# Grove_Base_Cape_for_BeagleBone_v2_0.net
KiCad netlist of a schematic drawn in EAGLE
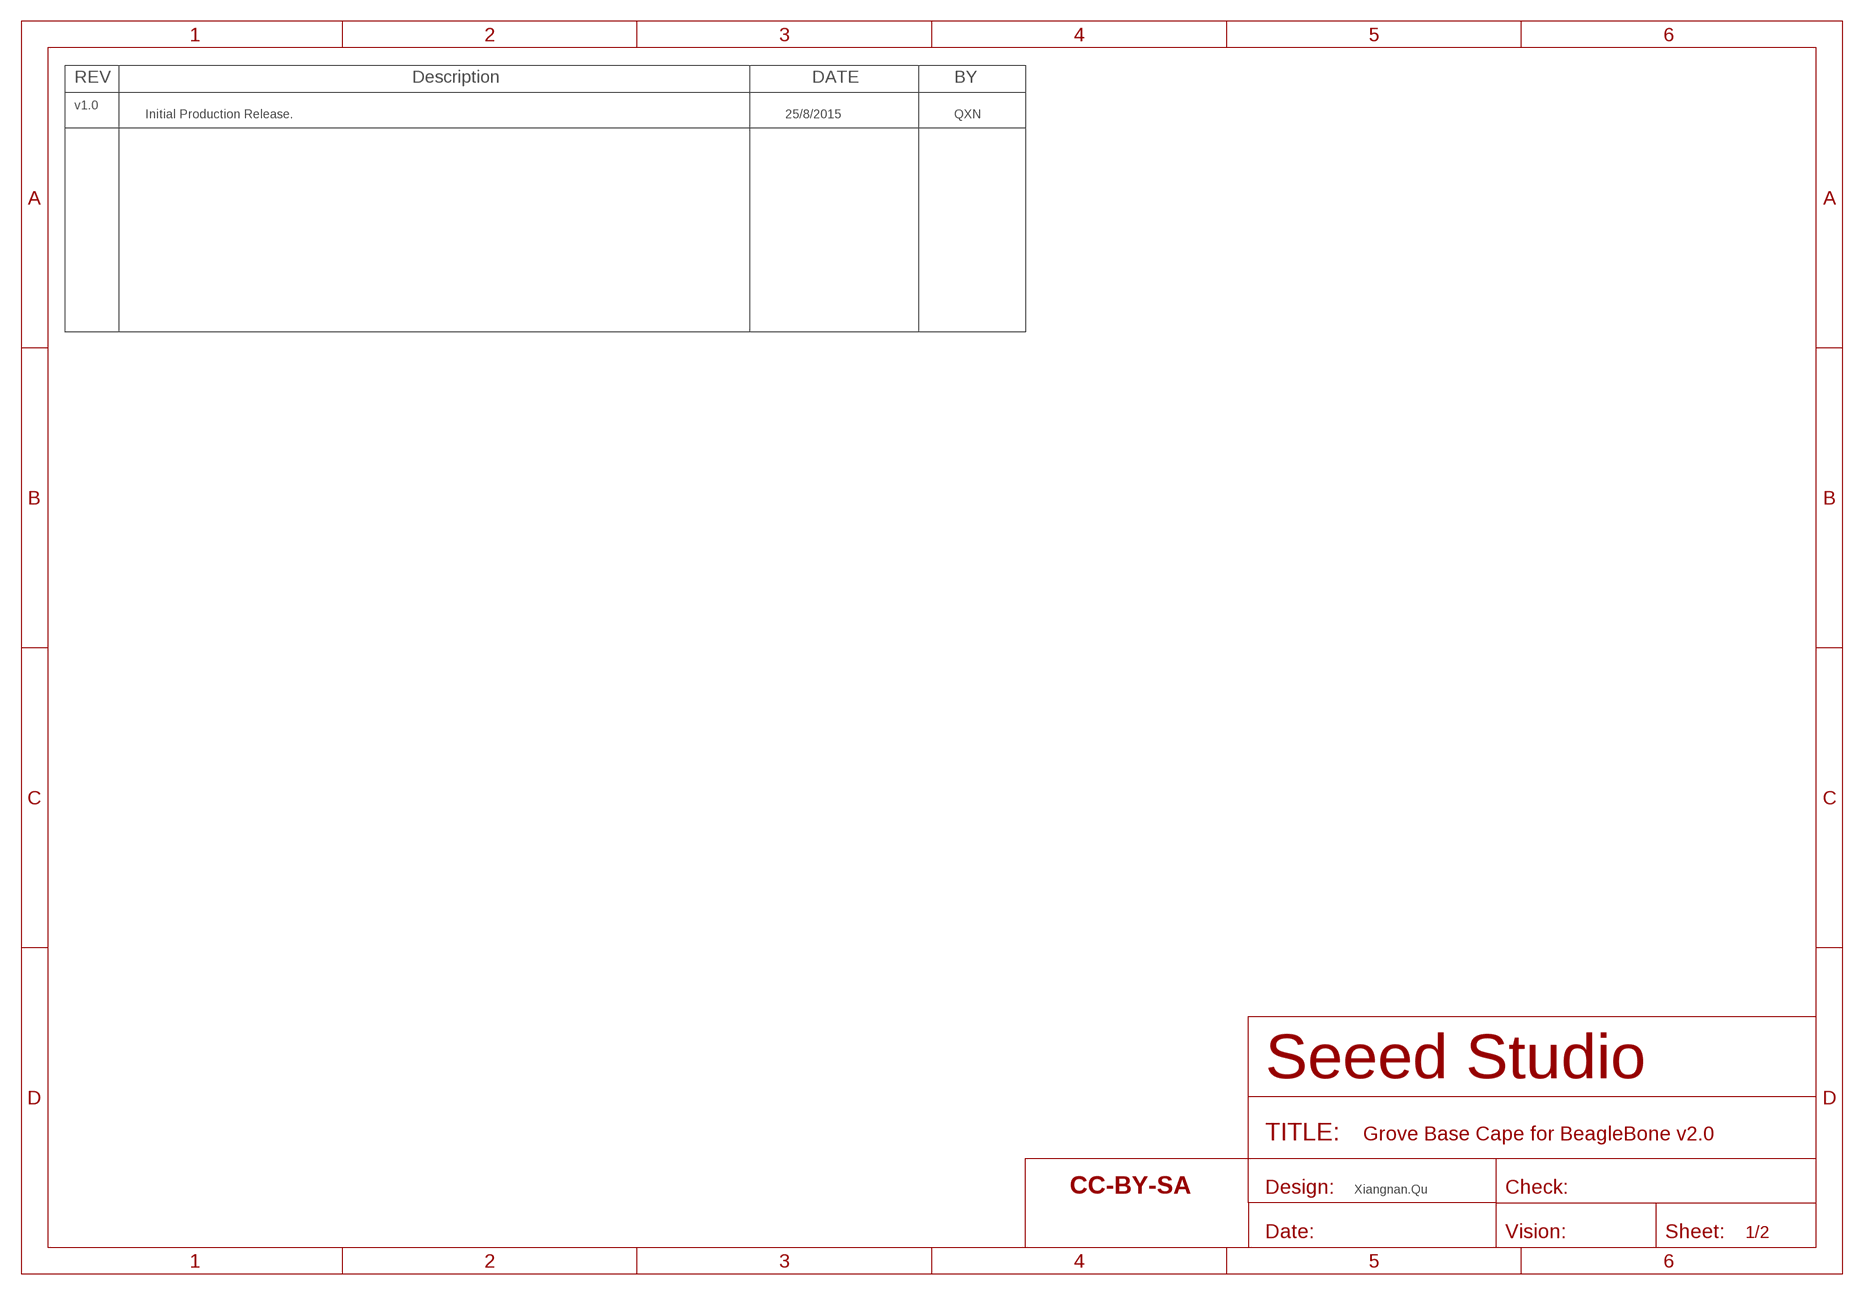
[diagram p0: schematic, sheet 1]
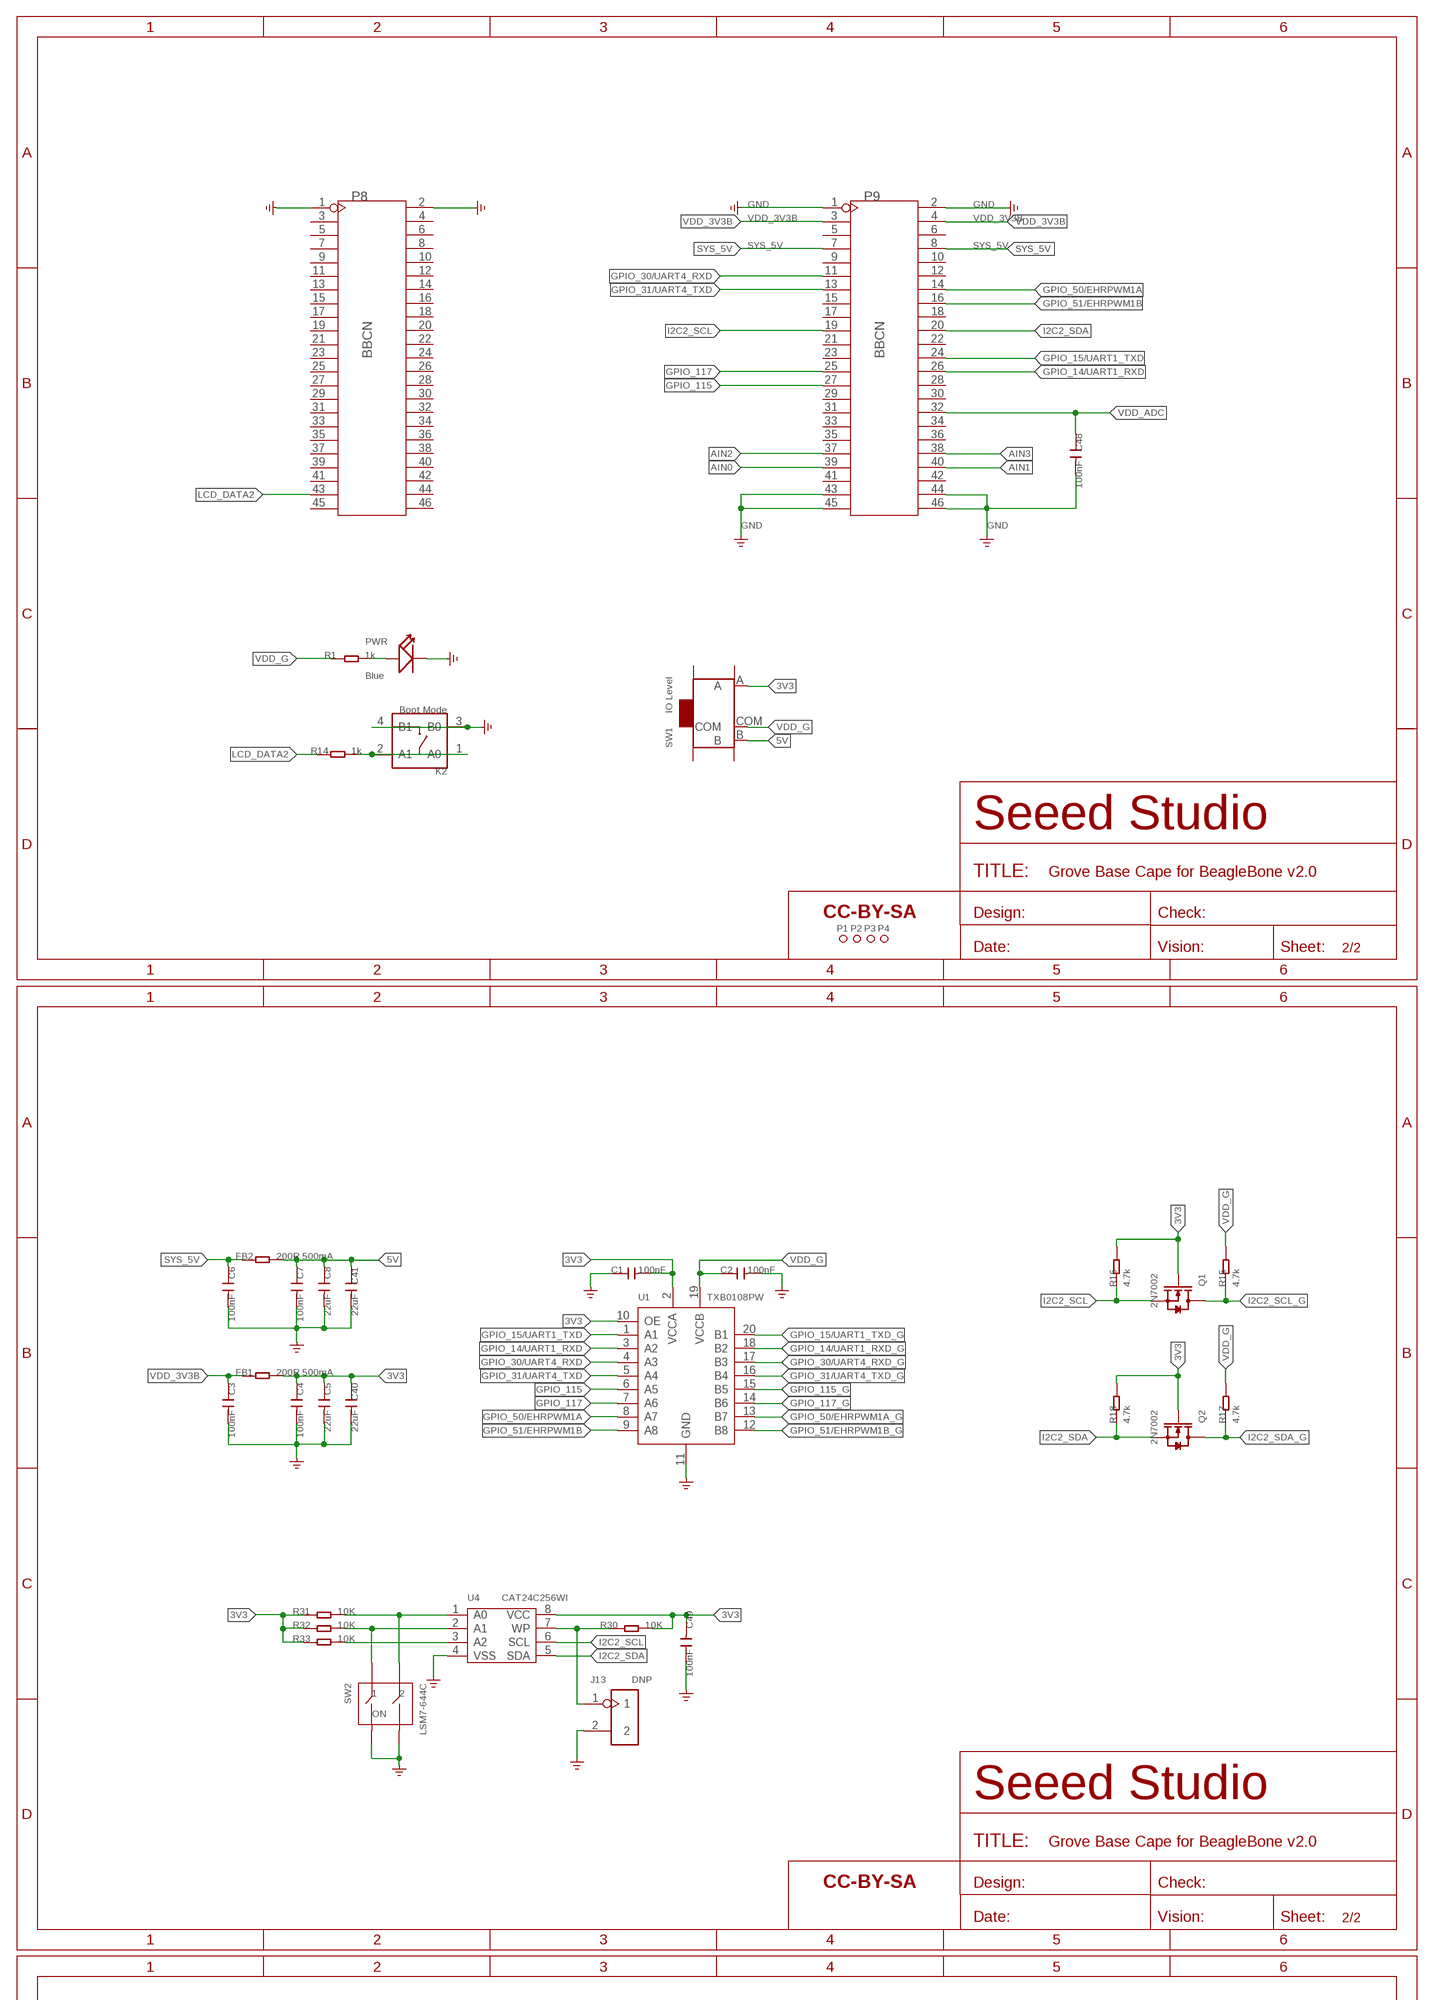
[diagram p1: schematic, sheet 2, part 1 of 2]
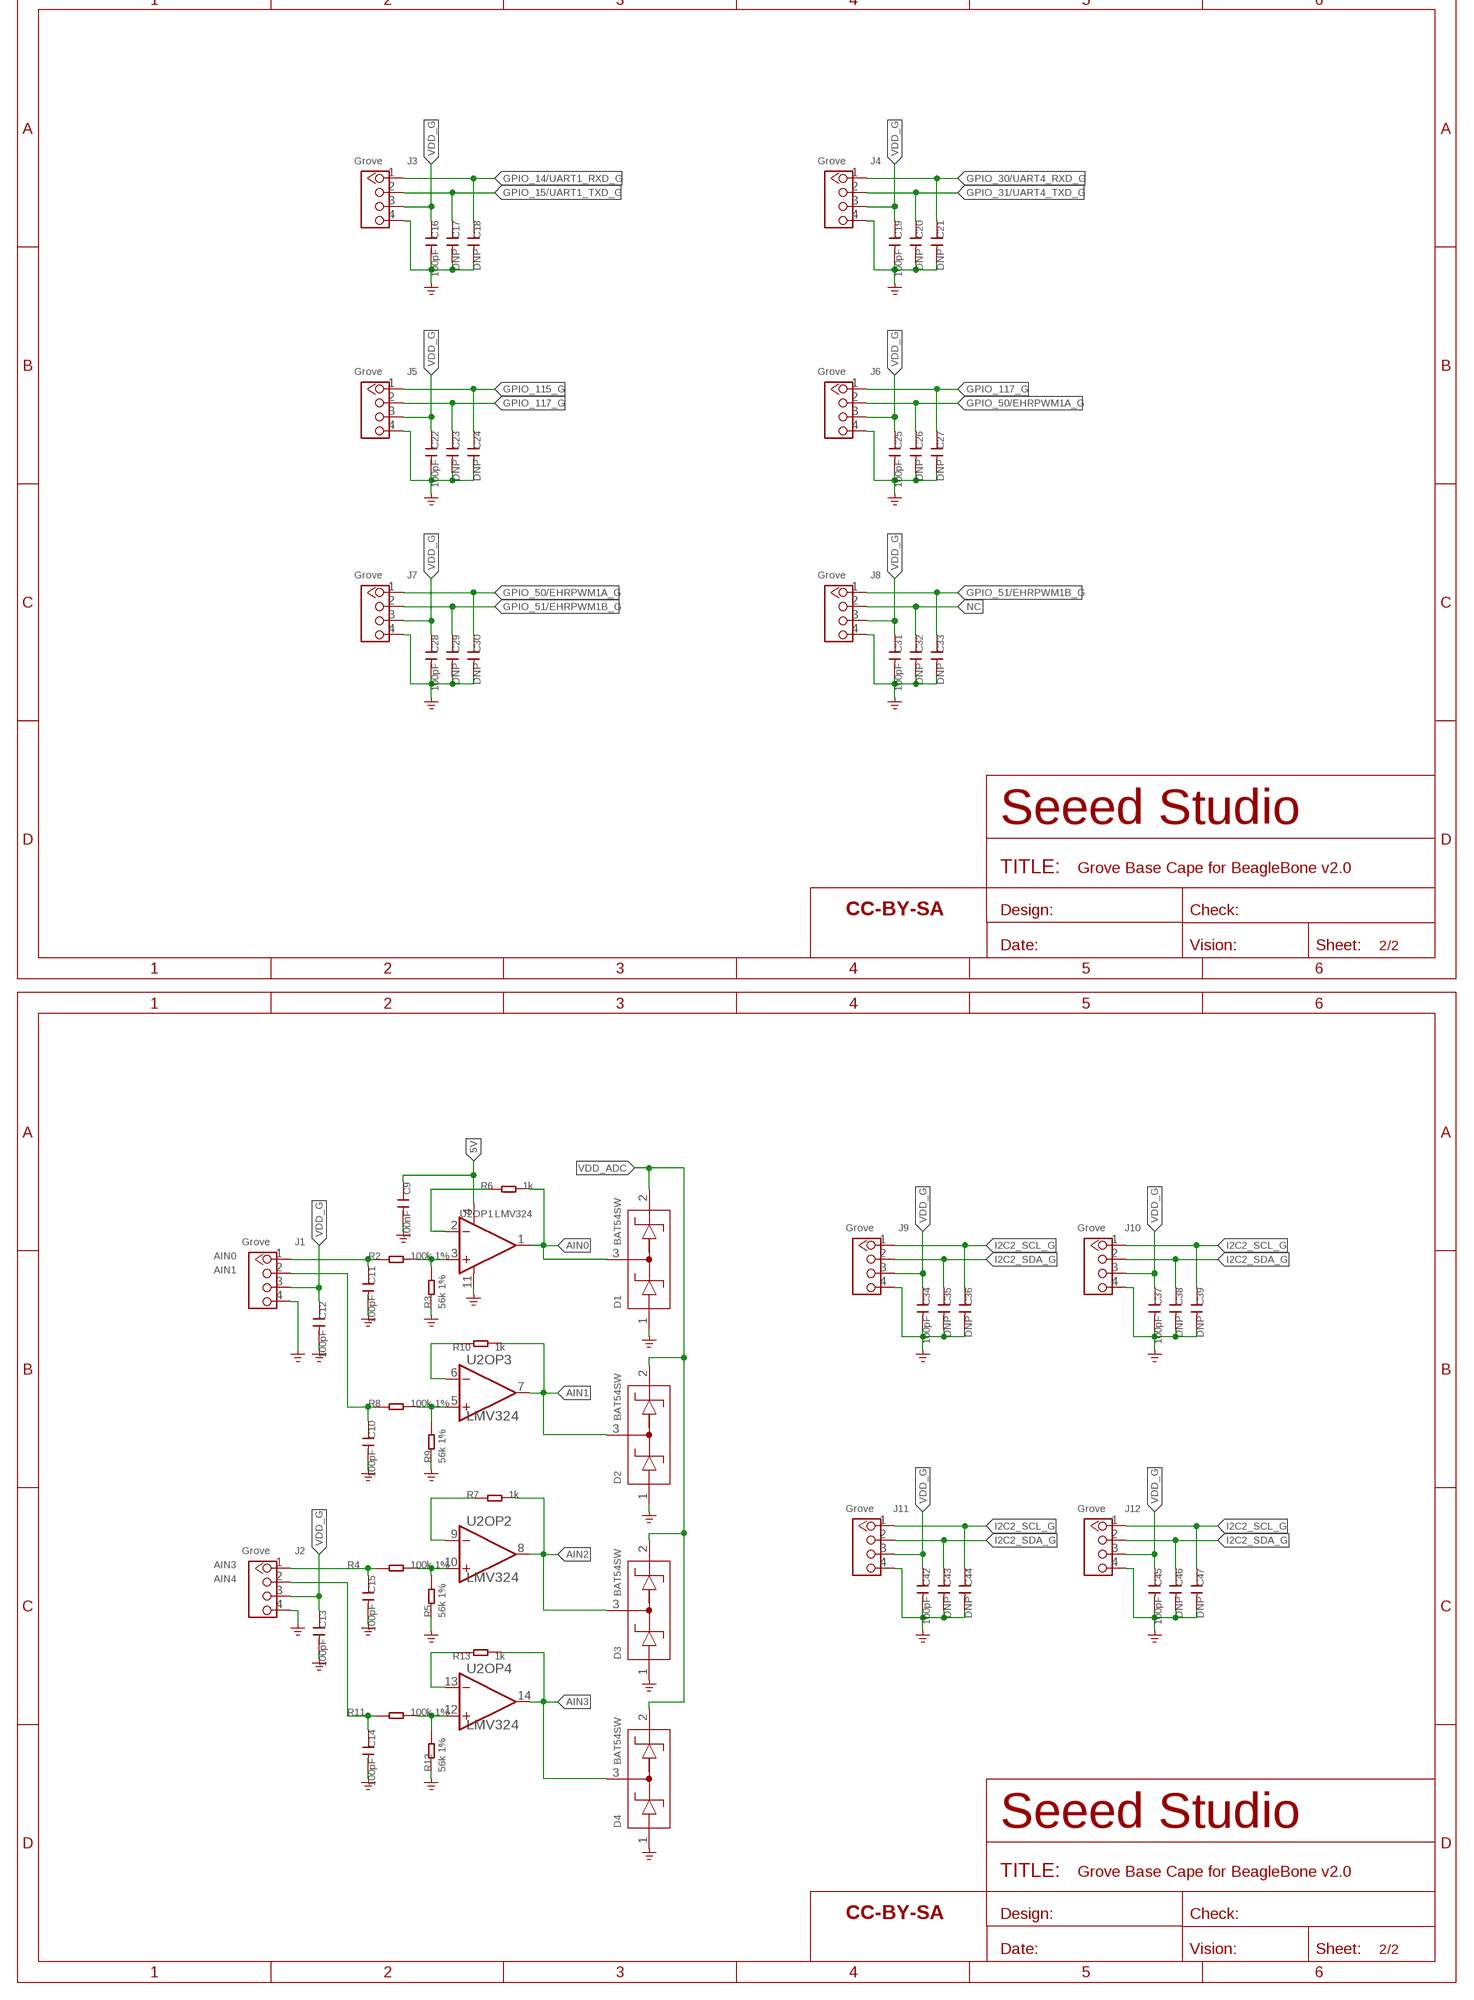
[diagram p2: schematic, sheet 2, part 2 of 2]

(export (version "E")
  (design (tool "Eeschema 10.0.6"))
  (components
    (comp (ref "C1")
      (value "100nF")
      (footprint "eagle-import:C0402")
      (libsource (lib "eagle-import") (part "CAP-0402"))
    )
    (comp (ref "C2")
      (value "100nF")
      (footprint "eagle-import:C0402")
      (libsource (lib "eagle-import") (part "CAP-0402"))
    )
    (comp (ref "C3")
      (value "100nF")
      (footprint "eagle-import:C0402")
      (libsource (lib "eagle-import") (part "CAP-0402"))
    )
    (comp (ref "C4")
      (value "100nF")
      (footprint "eagle-import:C0402")
      (libsource (lib "eagle-import") (part "CAP-0402"))
    )
    (comp (ref "C5")
      (value "22uF")
      (footprint "eagle-import:C0805")
      (libsource (lib "eagle-import") (part "CAP-0805"))
    )
    (comp (ref "C6")
      (value "100nF")
      (footprint "eagle-import:C0402")
      (libsource (lib "eagle-import") (part "CAP-0402"))
    )
    (comp (ref "C7")
      (value "100nF")
      (footprint "eagle-import:C0402")
      (libsource (lib "eagle-import") (part "CAP-0402"))
    )
    (comp (ref "C8")
      (value "22uF")
      (footprint "eagle-import:C0805")
      (libsource (lib "eagle-import") (part "CAP-0805"))
    )
    (comp (ref "C9")
      (value "100nF")
      (footprint "eagle-import:C0402")
      (libsource (lib "eagle-import") (part "CAP-0402"))
    )
    (comp (ref "C10")
      (value "100pF")
      (footprint "eagle-import:C0402")
      (libsource (lib "eagle-import") (part "CAP-0402"))
    )
    (comp (ref "C11")
      (value "100pF")
      (footprint "eagle-import:C0402")
      (libsource (lib "eagle-import") (part "CAP-0402"))
    )
    (comp (ref "C12")
      (value "100pF")
      (footprint "eagle-import:C0402")
      (libsource (lib "eagle-import") (part "CAP-0402"))
    )
    (comp (ref "C13")
      (value "100pF")
      (footprint "eagle-import:C0402")
      (libsource (lib "eagle-import") (part "CAP-0402"))
    )
    (comp (ref "C14")
      (value "100pF")
      (footprint "eagle-import:C0402")
      (libsource (lib "eagle-import") (part "CAP-0402"))
    )
    (comp (ref "C15")
      (value "100pF")
      (footprint "eagle-import:C0402")
      (libsource (lib "eagle-import") (part "CAP-0402"))
    )
    (comp (ref "C16")
      (value "100pF")
      (footprint "eagle-import:C0402")
      (libsource (lib "eagle-import") (part "CAP-0402"))
    )
    (comp (ref "C17")
      (value "DNP")
      (footprint "eagle-import:C0402")
      (libsource (lib "eagle-import") (part "CAP-0402"))
    )
    (comp (ref "C18")
      (value "DNP")
      (footprint "eagle-import:C0402")
      (libsource (lib "eagle-import") (part "CAP-0402"))
    )
    (comp (ref "C19")
      (value "100pF")
      (footprint "eagle-import:C0402")
      (libsource (lib "eagle-import") (part "CAP-0402"))
    )
    (comp (ref "C20")
      (value "DNP")
      (footprint "eagle-import:C0402")
      (libsource (lib "eagle-import") (part "CAP-0402"))
    )
    (comp (ref "C21")
      (value "DNP")
      (footprint "eagle-import:C0402")
      (libsource (lib "eagle-import") (part "CAP-0402"))
    )
    (comp (ref "C22")
      (value "100pF")
      (footprint "eagle-import:C0402")
      (libsource (lib "eagle-import") (part "CAP-0402"))
    )
    (comp (ref "C23")
      (value "DNP")
      (footprint "eagle-import:C0402")
      (libsource (lib "eagle-import") (part "CAP-0402"))
    )
    (comp (ref "C24")
      (value "DNP")
      (footprint "eagle-import:C0402")
      (libsource (lib "eagle-import") (part "CAP-0402"))
    )
    (comp (ref "C25")
      (value "100pF")
      (footprint "eagle-import:C0402")
      (libsource (lib "eagle-import") (part "CAP-0402"))
    )
    (comp (ref "C26")
      (value "DNP")
      (footprint "eagle-import:C0402")
      (libsource (lib "eagle-import") (part "CAP-0402"))
    )
    (comp (ref "C27")
      (value "DNP")
      (footprint "eagle-import:C0402")
      (libsource (lib "eagle-import") (part "CAP-0402"))
    )
    (comp (ref "C28")
      (value "100pF")
      (footprint "eagle-import:C0402")
      (libsource (lib "eagle-import") (part "CAP-0402"))
    )
    (comp (ref "C29")
      (value "DNP")
      (footprint "eagle-import:C0402")
      (libsource (lib "eagle-import") (part "CAP-0402"))
    )
    (comp (ref "C30")
      (value "DNP")
      (footprint "eagle-import:C0402")
      (libsource (lib "eagle-import") (part "CAP-0402"))
    )
    (comp (ref "C31")
      (value "100pF")
      (footprint "eagle-import:C0402")
      (libsource (lib "eagle-import") (part "CAP-0402"))
    )
    (comp (ref "C32")
      (value "DNP")
      (footprint "eagle-import:C0402")
      (libsource (lib "eagle-import") (part "CAP-0402"))
    )
    (comp (ref "C33")
      (value "DNP")
      (footprint "eagle-import:C0402")
      (libsource (lib "eagle-import") (part "CAP-0402"))
    )
    (comp (ref "C34")
      (value "100pF")
      (footprint "eagle-import:C0402")
      (libsource (lib "eagle-import") (part "CAP-0402"))
    )
    (comp (ref "C35")
      (value "DNP")
      (footprint "eagle-import:C0402")
      (libsource (lib "eagle-import") (part "CAP-0402"))
    )
    (comp (ref "C36")
      (value "DNP")
      (footprint "eagle-import:C0402")
      (libsource (lib "eagle-import") (part "CAP-0402"))
    )
    (comp (ref "C37")
      (value "100pF")
      (footprint "eagle-import:C0402")
      (libsource (lib "eagle-import") (part "CAP-0402"))
    )
    (comp (ref "C38")
      (value "DNP")
      (footprint "eagle-import:C0402")
      (libsource (lib "eagle-import") (part "CAP-0402"))
    )
    (comp (ref "C39")
      (value "DNP")
      (footprint "eagle-import:C0402")
      (libsource (lib "eagle-import") (part "CAP-0402"))
    )
    (comp (ref "C40")
      (value "22uF")
      (footprint "eagle-import:C0805")
      (libsource (lib "eagle-import") (part "CAP-0805"))
    )
    (comp (ref "C41")
      (value "22uF")
      (footprint "eagle-import:C0805")
      (libsource (lib "eagle-import") (part "CAP-0805"))
    )
    (comp (ref "C42")
      (value "100pF")
      (footprint "eagle-import:C0402")
      (libsource (lib "eagle-import") (part "CAP-0402"))
    )
    (comp (ref "C43")
      (value "DNP")
      (footprint "eagle-import:C0402")
      (libsource (lib "eagle-import") (part "CAP-0402"))
    )
    (comp (ref "C44")
      (value "DNP")
      (footprint "eagle-import:C0402")
      (libsource (lib "eagle-import") (part "CAP-0402"))
    )
    (comp (ref "C45")
      (value "100pF")
      (footprint "eagle-import:C0402")
      (libsource (lib "eagle-import") (part "CAP-0402"))
    )
    (comp (ref "C46")
      (value "DNP")
      (footprint "eagle-import:C0402")
      (libsource (lib "eagle-import") (part "CAP-0402"))
    )
    (comp (ref "C47")
      (value "DNP")
      (footprint "eagle-import:C0402")
      (libsource (lib "eagle-import") (part "CAP-0402"))
    )
    (comp (ref "C48")
      (value "100nF")
      (footprint "eagle-import:C0402")
      (libsource (lib "eagle-import") (part "CAP-0402"))
    )
    (comp (ref "C49")
      (value "100nF")
      (footprint "eagle-import:C0402")
      (libsource (lib "eagle-import") (part "CAP-0402"))
    )
    (comp (ref "D1")
      (value "BAT54SW")
      (footprint "eagle-import:SOT-23")
      (libsource (lib "eagle-import") (part "D-SCHOTTKY-3P（BAT54SW)"))
    )
    (comp (ref "D2")
      (value "BAT54SW")
      (footprint "eagle-import:SOT-23")
      (libsource (lib "eagle-import") (part "D-SCHOTTKY-3P（BAT54SW)"))
    )
    (comp (ref "D3")
      (value "BAT54SW")
      (footprint "eagle-import:SOT-23")
      (libsource (lib "eagle-import") (part "D-SCHOTTKY-3P（BAT54SW)"))
    )
    (comp (ref "D4")
      (value "BAT54SW")
      (footprint "eagle-import:SOT-23")
      (libsource (lib "eagle-import") (part "D-SCHOTTKY-3P（BAT54SW)"))
    )
    (comp (ref "FB1")
      (value "200R 500mA")
      (footprint "eagle-import:R0603")
      (libsource (lib "eagle-import") (part "RES-0603"))
    )
    (comp (ref "FB2")
      (value "200R 500mA")
      (footprint "eagle-import:R0603")
      (libsource (lib "eagle-import") (part "RES-0603"))
    )
    (comp (ref "FR2")
      (value "SEEEDSTUDIO-OPEN-SCH-FRAME")
      (footprint "eagle-import:SEEEDSTUDIO-PCB-FRAME")
      (libsource (lib "eagle-import") (part "SEEEDSTUDIO-OPEN-SCH-FRAME"))
    )
    (comp (ref "FR3")
      (value "SEEEDSTUDIO-OPEN-SCH-FRAME")
      (footprint "eagle-import:SEEEDSTUDIO-PCB-FRAME")
      (libsource (lib "eagle-import") (part "SEEEDSTUDIO-OPEN-SCH-FRAME"))
    )
    (comp (ref "FR4")
      (value "SEEEDSTUDIO-OPEN-SCH-FRAME")
      (footprint "eagle-import:SEEEDSTUDIO-PCB-FRAME")
      (libsource (lib "eagle-import") (part "SEEEDSTUDIO-OPEN-SCH-FRAME"))
    )
    (comp (ref "FR5")
      (value "SEEEDSTUDIO-OPEN-SCH-FRAME")
      (footprint "eagle-import:SEEEDSTUDIO-PCB-FRAME")
      (libsource (lib "eagle-import") (part "SEEEDSTUDIO-OPEN-SCH-FRAME"))
    )
    (comp (ref "J1")
      (value "Grove")
      (footprint "eagle-import:HW4-2.0")
      (libsource (lib "eagle-import") (part "GROVE-CONNECTOR-DIP-2.0"))
    )
    (comp (ref "J2")
      (value "Grove")
      (footprint "eagle-import:HW4-2.0")
      (libsource (lib "eagle-import") (part "GROVE-CONNECTOR-DIP-2.0"))
    )
    (comp (ref "J3")
      (value "Grove")
      (footprint "eagle-import:HW4-2.0")
      (libsource (lib "eagle-import") (part "GROVE-CONNECTOR-DIP-2.0"))
    )
    (comp (ref "J4")
      (value "Grove")
      (footprint "eagle-import:HW4-2.0")
      (libsource (lib "eagle-import") (part "GROVE-CONNECTOR-DIP-2.0"))
    )
    (comp (ref "J5")
      (value "Grove")
      (footprint "eagle-import:HW4-2.0")
      (libsource (lib "eagle-import") (part "GROVE-CONNECTOR-DIP-2.0"))
    )
    (comp (ref "J6")
      (value "Grove")
      (footprint "eagle-import:HW4-2.0")
      (libsource (lib "eagle-import") (part "GROVE-CONNECTOR-DIP-2.0"))
    )
    (comp (ref "J7")
      (value "Grove")
      (footprint "eagle-import:HW4-2.0")
      (libsource (lib "eagle-import") (part "GROVE-CONNECTOR-DIP-2.0"))
    )
    (comp (ref "J8")
      (value "Grove")
      (footprint "eagle-import:HW4-2.0")
      (libsource (lib "eagle-import") (part "GROVE-CONNECTOR-DIP-2.0"))
    )
    (comp (ref "J9")
      (value "Grove")
      (footprint "eagle-import:HW4-2.0")
      (libsource (lib "eagle-import") (part "GROVE-CONNECTOR-DIP-2.0"))
    )
    (comp (ref "J10")
      (value "Grove")
      (footprint "eagle-import:HW4-2.0")
      (libsource (lib "eagle-import") (part "GROVE-CONNECTOR-DIP-2.0"))
    )
    (comp (ref "J11")
      (value "Grove")
      (footprint "eagle-import:HW4-2.0")
      (libsource (lib "eagle-import") (part "GROVE-CONNECTOR-DIP-2.0"))
    )
    (comp (ref "J12")
      (value "Grove")
      (footprint "eagle-import:HW4-2.0")
      (libsource (lib "eagle-import") (part "GROVE-CONNECTOR-DIP-2.0"))
    )
    (comp (ref "J13")
      (value "DNP")
      (footprint "eagle-import:H2-1.5")
      (libsource (lib "eagle-import") (part "HEADER-2P-1.5"))
    )
    (comp (ref "K2")
      (value "Boot Mode")
      (footprint "eagle-import:SW4P-SMD-4.5X3.2X2.5MM")
      (libsource (lib "eagle-import") (part "BUTTON-4P-4.5X3.2"))
    )
    (comp (ref "P1")
      (value "MARK-1.0'ANNULAR'")
      (footprint "eagle-import:ROUND-MARK-1.0")
      (fields (field (name "PARTNO") "DNP"))
      (libsource (lib "eagle-import") (part "MARK-1.0'ANNULAR'"))
    )
    (comp (ref "P2")
      (value "MARK-1.0'ANNULAR'")
      (footprint "eagle-import:ROUND-MARK-1.0")
      (fields (field (name "PARTNO") "DNP"))
      (libsource (lib "eagle-import") (part "MARK-1.0'ANNULAR'"))
    )
    (comp (ref "P3")
      (value "MARK-1.0'ANNULAR'")
      (footprint "eagle-import:ROUND-MARK-1.0")
      (fields (field (name "PARTNO") "DNP"))
      (libsource (lib "eagle-import") (part "MARK-1.0'ANNULAR'"))
    )
    (comp (ref "P4")
      (value "MARK-1.0'ANNULAR'")
      (footprint "eagle-import:ROUND-MARK-1.0")
      (fields (field (name "PARTNO") "DNP"))
      (libsource (lib "eagle-import") (part "MARK-1.0'ANNULAR'"))
    )
    (comp (ref "P8")
      (value "BBCN")
      (footprint "eagle-import:2X23P-2.54")
      (libsource (lib "eagle-import") (part "HEADER-2X23P"))
    )
    (comp (ref "P9")
      (value "BBCN")
      (footprint "eagle-import:2X23P-2.54")
      (libsource (lib "eagle-import") (part "HEADER-2X23P"))
    )
    (comp (ref "PWR")
      (value "Blue")
      (footprint "eagle-import:LED-0402")
      (libsource (lib "eagle-import") (part "LED-0402"))
    )
    (comp (ref "Q1")
      (value "2N7002")
      (footprint "eagle-import:SOT-23")
      (libsource (lib "eagle-import") (part "MOSFET-N'SOT23'"))
    )
    (comp (ref "Q2")
      (value "2N7002")
      (footprint "eagle-import:SOT-23")
      (libsource (lib "eagle-import") (part "MOSFET-N'SOT23'"))
    )
    (comp (ref "R1")
      (value "1k")
      (footprint "eagle-import:R0402")
      (libsource (lib "eagle-import") (part "RES-0402"))
    )
    (comp (ref "R2")
      (value "100k 1%")
      (footprint "eagle-import:R0402")
      (libsource (lib "eagle-import") (part "RES-0402"))
    )
    (comp (ref "R3")
      (value "56k 1%")
      (footprint "eagle-import:R0402")
      (libsource (lib "eagle-import") (part "RES-0402"))
    )
    (comp (ref "R4")
      (value "100k 1%")
      (footprint "eagle-import:R0402")
      (libsource (lib "eagle-import") (part "RES-0402"))
    )
    (comp (ref "R5")
      (value "56k 1%")
      (footprint "eagle-import:R0402")
      (libsource (lib "eagle-import") (part "RES-0402"))
    )
    (comp (ref "R6")
      (value "1k")
      (footprint "eagle-import:R0402")
      (libsource (lib "eagle-import") (part "RES-0402"))
    )
    (comp (ref "R7")
      (value "1k")
      (footprint "eagle-import:R0402")
      (libsource (lib "eagle-import") (part "RES-0402"))
    )
    (comp (ref "R8")
      (value "100k 1%")
      (footprint "eagle-import:R0402")
      (libsource (lib "eagle-import") (part "RES-0402"))
    )
    (comp (ref "R9")
      (value "56k 1%")
      (footprint "eagle-import:R0402")
      (libsource (lib "eagle-import") (part "RES-0402"))
    )
    (comp (ref "R10")
      (value "1k")
      (footprint "eagle-import:R0402")
      (libsource (lib "eagle-import") (part "RES-0402"))
    )
    (comp (ref "R11")
      (value "100k 1%")
      (footprint "eagle-import:R0402")
      (libsource (lib "eagle-import") (part "RES-0402"))
    )
    (comp (ref "R12")
      (value "56k 1%")
      (footprint "eagle-import:R0402")
      (libsource (lib "eagle-import") (part "RES-0402"))
    )
    (comp (ref "R13")
      (value "1k")
      (footprint "eagle-import:R0402")
      (libsource (lib "eagle-import") (part "RES-0402"))
    )
    (comp (ref "R14")
      (value "1k")
      (footprint "eagle-import:R0402")
      (libsource (lib "eagle-import") (part "RES-0402"))
    )
    (comp (ref "R15")
      (value "4.7k")
      (footprint "eagle-import:R0402")
      (libsource (lib "eagle-import") (part "RES-0402"))
    )
    (comp (ref "R16")
      (value "4.7k")
      (footprint "eagle-import:R0402")
      (libsource (lib "eagle-import") (part "RES-0402"))
    )
    (comp (ref "R17")
      (value "4.7k")
      (footprint "eagle-import:R0402")
      (libsource (lib "eagle-import") (part "RES-0402"))
    )
    (comp (ref "R18")
      (value "4.7k")
      (footprint "eagle-import:R0402")
      (libsource (lib "eagle-import") (part "RES-0402"))
    )
    (comp (ref "R30")
      (value "10K")
      (footprint "eagle-import:R0402")
      (libsource (lib "eagle-import") (part "RES-0402"))
    )
    (comp (ref "R31")
      (value "10K")
      (footprint "eagle-import:R0402")
      (libsource (lib "eagle-import") (part "RES-0402"))
    )
    (comp (ref "R32")
      (value "10K")
      (footprint "eagle-import:R0402")
      (libsource (lib "eagle-import") (part "RES-0402"))
    )
    (comp (ref "R33")
      (value "10K")
      (footprint "eagle-import:R0402")
      (libsource (lib "eagle-import") (part "RES-0402"))
    )
    (comp (ref "SW1")
      (value "IO Level")
      (footprint "eagle-import:SW7-SMD-L6.7X2.7X3.2MM")
      (libsource (lib "eagle-import") (part "SWITCH-3+4P"))
    )
    (comp (ref "SW2")
      (value "LSM7-644C")
      (footprint "eagle-import:SW4-SMD-5.08X6.8X3.3MM")
      (libsource (lib "eagle-import") (part "SWITCHES-4P'KM-02'"))
    )
    (comp (ref "U1")
      (value "TXB0108PW")
      (footprint "eagle-import:TSSOP20-0.65-6.5X4.4MM")
      (libsource (lib "eagle-import") (part "LOGIC-TXS0108EPWR"))
    )
    (comp (ref "U2")
      (value "LMV324")
      (footprint "eagle-import:TSSOP14-0.65-5X4.4MM")
      (libsource (lib "eagle-import") (part "AMPLIFIER-LMV324'PW'"))
    )
    (comp (ref "U4")
      (value "CAT24C256WI")
      (footprint "eagle-import:SOIC8-1.27-5X4MM")
      (libsource (lib "eagle-import") (part "MCU-EEPROM-CAT24C256"))
    )
    (comp (ref "FR1")
      (value "SEEEDSTUDIO-OPEN-SCH-FRAME")
      (footprint "eagle-import:SEEEDSTUDIO-PCB-FRAME")
      (libsource (lib "eagle-import") (part "SEEEDSTUDIO-OPEN-SCH-FRAME"))
    )
  )
  (nets
    (net (code "1") (name "3V3") (class "Default")
      (node (ref "C1") (pin "2") (pinfunction "2_2") (pintype "passive"))
      (node (ref "C4") (pin "1") (pinfunction "1_1") (pintype "passive"))
      (node (ref "C40") (pin "1") (pinfunction "1_1") (pintype "passive"))
      (node (ref "C49") (pin "2") (pinfunction "2_2") (pintype "passive"))
      (node (ref "C5") (pin "1") (pinfunction "1_1") (pintype "passive"))
      (node (ref "FB1") (pin "2") (pinfunction "2_2") (pintype "passive"))
      (node (ref "Q1") (pin "1") (pinfunction "G_1") (pintype "passive"))
      (node (ref "Q2") (pin "1") (pinfunction "G_1") (pintype "passive"))
      (node (ref "R16") (pin "2") (pinfunction "2_2") (pintype "passive"))
      (node (ref "R18") (pin "2") (pinfunction "2_2") (pintype "passive"))
      (node (ref "R30") (pin "1") (pinfunction "1_1") (pintype "passive"))
      (node (ref "R31") (pin "2") (pinfunction "2_2") (pintype "passive"))
      (node (ref "R32") (pin "2") (pinfunction "2_2") (pintype "passive"))
      (node (ref "R33") (pin "2") (pinfunction "2_2") (pintype "passive"))
      (node (ref "SW1") (pin "A") (pinfunction "A_A") (pintype "bidirectional"))
      (node (ref "U1") (pin "10") (pinfunction "OE_10") (pintype "bidirectional"))
      (node (ref "U1") (pin "2") (pinfunction "VCCA_2") (pintype "bidirectional"))
      (node (ref "U4") (pin "8") (pinfunction "VCC_8") (pintype "bidirectional"))
    )
    (net (code "2") (name "5V") (class "Default")
      (node (ref "C41") (pin "1") (pinfunction "1_1") (pintype "passive"))
      (node (ref "C7") (pin "1") (pinfunction "1_1") (pintype "passive"))
      (node (ref "C8") (pin "1") (pinfunction "1_1") (pintype "passive"))
      (node (ref "C9") (pin "1") (pinfunction "1_1") (pintype "passive"))
      (node (ref "FB2") (pin "2") (pinfunction "2_2") (pintype "passive"))
      (node (ref "SW1") (pin "B") (pinfunction "B_B") (pintype "bidirectional"))
      (node (ref "U2") (pin "4") (pinfunction "V+_4") (pintype "power_in"))
    )
    (net (code "3") (name "AIN0") (class "Default")
      (node (ref "D1") (pin "3") (pinfunction "3_3") (pintype "bidirectional"))
      (node (ref "P9") (pin "39") (pinfunction "39_39") (pintype "bidirectional"))
      (node (ref "R6") (pin "2") (pinfunction "2_2") (pintype "passive"))
      (node (ref "U2") (pin "1") (pinfunction "OUT_1") (pintype "output"))
    )
    (net (code "4") (name "AIN1") (class "Default")
      (node (ref "D2") (pin "3") (pinfunction "3_3") (pintype "bidirectional"))
      (node (ref "P9") (pin "40") (pinfunction "40_40") (pintype "bidirectional"))
      (node (ref "R10") (pin "2") (pinfunction "2_2") (pintype "passive"))
      (node (ref "U2") (pin "7") (pinfunction "OUT_7") (pintype "output"))
    )
    (net (code "5") (name "AIN2") (class "Default")
      (node (ref "D3") (pin "3") (pinfunction "3_3") (pintype "bidirectional"))
      (node (ref "P9") (pin "37") (pinfunction "37_37") (pintype "bidirectional"))
      (node (ref "R7") (pin "2") (pinfunction "2_2") (pintype "passive"))
      (node (ref "U2") (pin "8") (pinfunction "OUT_8") (pintype "output"))
    )
    (net (code "6") (name "AIN3") (class "Default")
      (node (ref "D4") (pin "3") (pinfunction "3_3") (pintype "bidirectional"))
      (node (ref "P9") (pin "38") (pinfunction "38_38") (pintype "bidirectional"))
      (node (ref "R13") (pin "2") (pinfunction "2_2") (pintype "passive"))
      (node (ref "U2") (pin "14") (pinfunction "OUT_14") (pintype "output"))
    )
    (net (code "7") (name "GND") (class "Default")
      (node (ref "C1") (pin "1") (pinfunction "1_1") (pintype "passive"))
      (node (ref "C10") (pin "2") (pinfunction "2_2") (pintype "passive"))
      (node (ref "C11") (pin "2") (pinfunction "2_2") (pintype "passive"))
      (node (ref "C12") (pin "2") (pinfunction "2_2") (pintype "passive"))
      (node (ref "C13") (pin "2") (pinfunction "2_2") (pintype "passive"))
      (node (ref "C14") (pin "2") (pinfunction "2_2") (pintype "passive"))
      (node (ref "C15") (pin "2") (pinfunction "2_2") (pintype "passive"))
      (node (ref "C16") (pin "2") (pinfunction "2_2") (pintype "passive"))
      (node (ref "C17") (pin "2") (pinfunction "2_2") (pintype "passive"))
      (node (ref "C18") (pin "2") (pinfunction "2_2") (pintype "passive"))
      (node (ref "C19") (pin "2") (pinfunction "2_2") (pintype "passive"))
      (node (ref "C2") (pin "2") (pinfunction "2_2") (pintype "passive"))
      (node (ref "C20") (pin "2") (pinfunction "2_2") (pintype "passive"))
      (node (ref "C21") (pin "2") (pinfunction "2_2") (pintype "passive"))
      (node (ref "C22") (pin "2") (pinfunction "2_2") (pintype "passive"))
      (node (ref "C23") (pin "2") (pinfunction "2_2") (pintype "passive"))
      (node (ref "C24") (pin "2") (pinfunction "2_2") (pintype "passive"))
      (node (ref "C25") (pin "2") (pinfunction "2_2") (pintype "passive"))
      (node (ref "C26") (pin "2") (pinfunction "2_2") (pintype "passive"))
      (node (ref "C27") (pin "2") (pinfunction "2_2") (pintype "passive"))
      (node (ref "C28") (pin "2") (pinfunction "2_2") (pintype "passive"))
      (node (ref "C29") (pin "2") (pinfunction "2_2") (pintype "passive"))
      (node (ref "C3") (pin "2") (pinfunction "2_2") (pintype "passive"))
      (node (ref "C30") (pin "2") (pinfunction "2_2") (pintype "passive"))
      (node (ref "C31") (pin "2") (pinfunction "2_2") (pintype "passive"))
      (node (ref "C32") (pin "2") (pinfunction "2_2") (pintype "passive"))
      (node (ref "C33") (pin "2") (pinfunction "2_2") (pintype "passive"))
      (node (ref "C34") (pin "2") (pinfunction "2_2") (pintype "passive"))
      (node (ref "C35") (pin "2") (pinfunction "2_2") (pintype "passive"))
      (node (ref "C36") (pin "2") (pinfunction "2_2") (pintype "passive"))
      (node (ref "C37") (pin "2") (pinfunction "2_2") (pintype "passive"))
      (node (ref "C38") (pin "2") (pinfunction "2_2") (pintype "passive"))
      (node (ref "C39") (pin "2") (pinfunction "2_2") (pintype "passive"))
      (node (ref "C4") (pin "2") (pinfunction "2_2") (pintype "passive"))
      (node (ref "C40") (pin "2") (pinfunction "2_2") (pintype "passive"))
      (node (ref "C41") (pin "2") (pinfunction "2_2") (pintype "passive"))
      (node (ref "C42") (pin "2") (pinfunction "2_2") (pintype "passive"))
      (node (ref "C43") (pin "2") (pinfunction "2_2") (pintype "passive"))
      (node (ref "C44") (pin "2") (pinfunction "2_2") (pintype "passive"))
      (node (ref "C45") (pin "2") (pinfunction "2_2") (pintype "passive"))
      (node (ref "C46") (pin "2") (pinfunction "2_2") (pintype "passive"))
      (node (ref "C47") (pin "2") (pinfunction "2_2") (pintype "passive"))
      (node (ref "C48") (pin "2") (pinfunction "2_2") (pintype "passive"))
      (node (ref "C49") (pin "1") (pinfunction "1_1") (pintype "passive"))
      (node (ref "C5") (pin "2") (pinfunction "2_2") (pintype "passive"))
      (node (ref "C6") (pin "2") (pinfunction "2_2") (pintype "passive"))
      (node (ref "C7") (pin "2") (pinfunction "2_2") (pintype "passive"))
      (node (ref "C8") (pin "2") (pinfunction "2_2") (pintype "passive"))
      (node (ref "C9") (pin "2") (pinfunction "2_2") (pintype "passive"))
      (node (ref "D1") (pin "1") (pinfunction "1_1") (pintype "bidirectional"))
      (node (ref "D2") (pin "1") (pinfunction "1_1") (pintype "bidirectional"))
      (node (ref "D3") (pin "1") (pinfunction "1_1") (pintype "bidirectional"))
      (node (ref "D4") (pin "1") (pinfunction "1_1") (pintype "bidirectional"))
      (node (ref "J1") (pin "4") (pinfunction "4_4") (pintype "bidirectional"))
      (node (ref "J10") (pin "4") (pinfunction "4_4") (pintype "bidirectional"))
      (node (ref "J11") (pin "4") (pinfunction "4_4") (pintype "bidirectional"))
      (node (ref "J12") (pin "4") (pinfunction "4_4") (pintype "bidirectional"))
      (node (ref "J13") (pin "2") (pinfunction "2_2") (pintype "bidirectional"))
      (node (ref "J2") (pin "4") (pinfunction "4_4") (pintype "bidirectional"))
      (node (ref "J3") (pin "4") (pinfunction "4_4") (pintype "bidirectional"))
      (node (ref "J4") (pin "4") (pinfunction "4_4") (pintype "bidirectional"))
      (node (ref "J5") (pin "4") (pinfunction "4_4") (pintype "bidirectional"))
      (node (ref "J6") (pin "4") (pinfunction "4_4") (pintype "bidirectional"))
      (node (ref "J7") (pin "4") (pinfunction "4_4") (pintype "bidirectional"))
      (node (ref "J8") (pin "4") (pinfunction "4_4") (pintype "bidirectional"))
      (node (ref "J9") (pin "4") (pinfunction "4_4") (pintype "bidirectional"))
      (node (ref "K2") (pin "3") (pinfunction "B0_3") (pintype "bidirectional"))
      (node (ref "K2") (pin "4") (pinfunction "B1_4") (pintype "bidirectional"))
      (node (ref "P8") (pin "1") (pinfunction "1_1") (pintype "bidirectional"))
      (node (ref "P8") (pin "2") (pinfunction "2_2") (pintype "bidirectional"))
      (node (ref "P9") (pin "1") (pinfunction "1_1") (pintype "bidirectional"))
      (node (ref "P9") (pin "2") (pinfunction "2_2") (pintype "bidirectional"))
      (node (ref "P9") (pin "43") (pinfunction "43_43") (pintype "bidirectional"))
      (node (ref "P9") (pin "44") (pinfunction "44_44") (pintype "bidirectional"))
      (node (ref "P9") (pin "45") (pinfunction "45_45") (pintype "bidirectional"))
      (node (ref "P9") (pin "46") (pinfunction "46_46") (pintype "bidirectional"))
      (node (ref "PWR") (pin "-") (pinfunction "-_-") (pintype "passive"))
      (node (ref "R12") (pin "1") (pinfunction "1_1") (pintype "passive"))
      (node (ref "R3") (pin "1") (pinfunction "1_1") (pintype "passive"))
      (node (ref "R5") (pin "1") (pinfunction "1_1") (pintype "passive"))
      (node (ref "R9") (pin "1") (pinfunction "1_1") (pintype "passive"))
      (node (ref "SW2") (pin "3") (pinfunction "3_3") (pintype "bidirectional"))
      (node (ref "SW2") (pin "4") (pinfunction "4_4") (pintype "bidirectional"))
      (node (ref "U1") (pin "11") (pinfunction "GND_11") (pintype "bidirectional"))
      (node (ref "U2") (pin "11") (pinfunction "V-_11") (pintype "power_in"))
      (node (ref "U4") (pin "4") (pinfunction "VSS_4") (pintype "bidirectional"))
    )
    (net (code "8") (name "GPIO_14{slash}UART1_RXD") (class "Default")
      (node (ref "P9") (pin "26") (pinfunction "26_26") (pintype "bidirectional"))
      (node (ref "U1") (pin "3") (pinfunction "A2_3") (pintype "bidirectional"))
    )
    (net (code "9") (name "GPIO_14{slash}UART1_RXD_G") (class "Default")
      (node (ref "C18") (pin "1") (pinfunction "1_1") (pintype "passive"))
      (node (ref "J3") (pin "1") (pinfunction "1_1") (pintype "bidirectional"))
      (node (ref "U1") (pin "18") (pinfunction "B2_18") (pintype "bidirectional"))
    )
    (net (code "10") (name "GPIO_15{slash}UART1_TXD") (class "Default")
      (node (ref "P9") (pin "24") (pinfunction "24_24") (pintype "bidirectional"))
      (node (ref "U1") (pin "1") (pinfunction "A1_1") (pintype "bidirectional"))
    )
    (net (code "11") (name "GPIO_15{slash}UART1_TXD_G") (class "Default")
      (node (ref "C17") (pin "1") (pinfunction "1_1") (pintype "passive"))
      (node (ref "J3") (pin "2") (pinfunction "2_2") (pintype "bidirectional"))
      (node (ref "U1") (pin "20") (pinfunction "B1_20") (pintype "bidirectional"))
    )
    (net (code "12") (name "GPIO_30{slash}UART4_RXD") (class "Default")
      (node (ref "P9") (pin "11") (pinfunction "11_11") (pintype "bidirectional"))
      (node (ref "U1") (pin "4") (pinfunction "A3_4") (pintype "bidirectional"))
    )
    (net (code "13") (name "GPIO_30{slash}UART4_RXD_G") (class "Default")
      (node (ref "C21") (pin "1") (pinfunction "1_1") (pintype "passive"))
      (node (ref "J4") (pin "1") (pinfunction "1_1") (pintype "bidirectional"))
      (node (ref "U1") (pin "17") (pinfunction "B3_17") (pintype "bidirectional"))
    )
    (net (code "14") (name "GPIO_31{slash}UART4_TXD") (class "Default")
      (node (ref "P9") (pin "13") (pinfunction "13_13") (pintype "bidirectional"))
      (node (ref "U1") (pin "5") (pinfunction "A4_5") (pintype "bidirectional"))
    )
    (net (code "15") (name "GPIO_31{slash}UART4_TXD_G") (class "Default")
      (node (ref "C20") (pin "1") (pinfunction "1_1") (pintype "passive"))
      (node (ref "J4") (pin "2") (pinfunction "2_2") (pintype "bidirectional"))
      (node (ref "U1") (pin "16") (pinfunction "B4_16") (pintype "bidirectional"))
    )
    (net (code "16") (name "GPIO_50{slash}EHRPWM1A") (class "Default")
      (node (ref "P9") (pin "14") (pinfunction "14_14") (pintype "bidirectional"))
      (node (ref "U1") (pin "8") (pinfunction "A7_8") (pintype "bidirectional"))
    )
    (net (code "17") (name "GPIO_50{slash}EHRPWM1A_G") (class "Default")
      (node (ref "C26") (pin "1") (pinfunction "1_1") (pintype "passive"))
      (node (ref "C30") (pin "1") (pinfunction "1_1") (pintype "passive"))
      (node (ref "J6") (pin "2") (pinfunction "2_2") (pintype "bidirectional"))
      (node (ref "J7") (pin "1") (pinfunction "1_1") (pintype "bidirectional"))
      (node (ref "U1") (pin "13") (pinfunction "B7_13") (pintype "bidirectional"))
    )
    (net (code "18") (name "GPIO_51{slash}EHRPWM1B") (class "Default")
      (node (ref "P9") (pin "16") (pinfunction "16_16") (pintype "bidirectional"))
      (node (ref "U1") (pin "9") (pinfunction "A8_9") (pintype "bidirectional"))
    )
    (net (code "19") (name "GPIO_51{slash}EHRPWM1B_G") (class "Default")
      (node (ref "C29") (pin "1") (pinfunction "1_1") (pintype "passive"))
      (node (ref "C33") (pin "1") (pinfunction "1_1") (pintype "passive"))
      (node (ref "J7") (pin "2") (pinfunction "2_2") (pintype "bidirectional"))
      (node (ref "J8") (pin "1") (pinfunction "1_1") (pintype "bidirectional"))
      (node (ref "U1") (pin "12") (pinfunction "B8_12") (pintype "bidirectional"))
    )
    (net (code "20") (name "GPIO_115") (class "Default")
      (node (ref "P9") (pin "27") (pinfunction "27_27") (pintype "bidirectional"))
      (node (ref "U1") (pin "6") (pinfunction "A5_6") (pintype "bidirectional"))
    )
    (net (code "21") (name "GPIO_115_G") (class "Default")
      (node (ref "C24") (pin "1") (pinfunction "1_1") (pintype "passive"))
      (node (ref "J5") (pin "1") (pinfunction "1_1") (pintype "bidirectional"))
      (node (ref "U1") (pin "15") (pinfunction "B5_15") (pintype "bidirectional"))
    )
    (net (code "22") (name "GPIO_117") (class "Default")
      (node (ref "P9") (pin "25") (pinfunction "25_25") (pintype "bidirectional"))
      (node (ref "U1") (pin "7") (pinfunction "A6_7") (pintype "bidirectional"))
    )
    (net (code "23") (name "GPIO_117_G") (class "Default")
      (node (ref "C23") (pin "1") (pinfunction "1_1") (pintype "passive"))
      (node (ref "C27") (pin "1") (pinfunction "1_1") (pintype "passive"))
      (node (ref "J5") (pin "2") (pinfunction "2_2") (pintype "bidirectional"))
      (node (ref "J6") (pin "1") (pinfunction "1_1") (pintype "bidirectional"))
      (node (ref "U1") (pin "14") (pinfunction "B6_14") (pintype "bidirectional"))
    )
    (net (code "24") (name "I2C2_SCL") (class "Default")
      (node (ref "P9") (pin "19") (pinfunction "19_19") (pintype "bidirectional"))
      (node (ref "Q1") (pin "2") (pinfunction "S_2") (pintype "passive"))
      (node (ref "R16") (pin "1") (pinfunction "1_1") (pintype "passive"))
      (node (ref "U4") (pin "6") (pinfunction "SCL_6") (pintype "bidirectional"))
    )
    (net (code "25") (name "I2C2_SCL_G") (class "Default")
      (node (ref "C36") (pin "1") (pinfunction "1_1") (pintype "passive"))
      (node (ref "C39") (pin "1") (pinfunction "1_1") (pintype "passive"))
      (node (ref "C44") (pin "1") (pinfunction "1_1") (pintype "passive"))
      (node (ref "C47") (pin "1") (pinfunction "1_1") (pintype "passive"))
      (node (ref "J10") (pin "1") (pinfunction "1_1") (pintype "bidirectional"))
      (node (ref "J11") (pin "1") (pinfunction "1_1") (pintype "bidirectional"))
      (node (ref "J12") (pin "1") (pinfunction "1_1") (pintype "bidirectional"))
      (node (ref "J9") (pin "1") (pinfunction "1_1") (pintype "bidirectional"))
      (node (ref "Q1") (pin "3") (pinfunction "D_3") (pintype "passive"))
      (node (ref "R15") (pin "1") (pinfunction "1_1") (pintype "passive"))
    )
    (net (code "26") (name "I2C2_SDA") (class "Default")
      (node (ref "P9") (pin "20") (pinfunction "20_20") (pintype "bidirectional"))
      (node (ref "Q2") (pin "2") (pinfunction "S_2") (pintype "passive"))
      (node (ref "R18") (pin "1") (pinfunction "1_1") (pintype "passive"))
      (node (ref "U4") (pin "5") (pinfunction "SDA_5") (pintype "bidirectional"))
    )
    (net (code "27") (name "I2C2_SDA_G") (class "Default")
      (node (ref "C35") (pin "1") (pinfunction "1_1") (pintype "passive"))
      (node (ref "C38") (pin "1") (pinfunction "1_1") (pintype "passive"))
      (node (ref "C43") (pin "1") (pinfunction "1_1") (pintype "passive"))
      (node (ref "C46") (pin "1") (pinfunction "1_1") (pintype "passive"))
      (node (ref "J10") (pin "2") (pinfunction "2_2") (pintype "bidirectional"))
      (node (ref "J11") (pin "2") (pinfunction "2_2") (pintype "bidirectional"))
      (node (ref "J12") (pin "2") (pinfunction "2_2") (pintype "bidirectional"))
      (node (ref "J9") (pin "2") (pinfunction "2_2") (pintype "bidirectional"))
      (node (ref "Q2") (pin "3") (pinfunction "D_3") (pintype "passive"))
      (node (ref "R17") (pin "1") (pinfunction "1_1") (pintype "passive"))
    )
    (net (code "28") (name "LCD_DATA2") (class "Default")
      (node (ref "P8") (pin "43") (pinfunction "43_43") (pintype "bidirectional"))
      (node (ref "R14") (pin "1") (pinfunction "1_1") (pintype "passive"))
    )
    (net (code "29") (name "NC") (class "Default")
      (node (ref "C32") (pin "1") (pinfunction "1_1") (pintype "passive"))
      (node (ref "J8") (pin "2") (pinfunction "2_2") (pintype "bidirectional"))
    )
    (net (code "30") (name "Net-(C10-Pad1)") (class "Default")
      (node (ref "C10") (pin "1") (pinfunction "1_1") (pintype "passive"))
      (node (ref "J1") (pin "2") (pinfunction "2_2") (pintype "bidirectional"))
      (node (ref "R8") (pin "1") (pinfunction "1_1") (pintype "passive"))
    )
    (net (code "31") (name "Net-(C11-Pad1)") (class "Default")
      (node (ref "C11") (pin "1") (pinfunction "1_1") (pintype "passive"))
      (node (ref "J1") (pin "1") (pinfunction "1_1") (pintype "bidirectional"))
      (node (ref "R2") (pin "1") (pinfunction "1_1") (pintype "passive"))
    )
    (net (code "32") (name "Net-(C14-Pad1)") (class "Default")
      (node (ref "C14") (pin "1") (pinfunction "1_1") (pintype "passive"))
      (node (ref "J2") (pin "2") (pinfunction "2_2") (pintype "bidirectional"))
      (node (ref "R11") (pin "1") (pinfunction "1_1") (pintype "passive"))
    )
    (net (code "33") (name "Net-(C15-Pad1)") (class "Default")
      (node (ref "C15") (pin "1") (pinfunction "1_1") (pintype "passive"))
      (node (ref "J2") (pin "1") (pinfunction "1_1") (pintype "bidirectional"))
      (node (ref "R4") (pin "1") (pinfunction "1_1") (pintype "passive"))
    )
    (net (code "34") (name "Net-(K2-A0)") (class "Default")
      (node (ref "K2") (pin "1") (pinfunction "A0_1") (pintype "bidirectional"))
      (node (ref "K2") (pin "2") (pinfunction "A1_2") (pintype "bidirectional"))
      (node (ref "R14") (pin "2") (pinfunction "2_2") (pintype "passive"))
    )
    (net (code "35") (name "Net-(PWR-Pad+)") (class "Default")
      (node (ref "PWR") (pin "+") (pinfunction "+_+") (pintype "passive"))
      (node (ref "R1") (pin "2") (pinfunction "2_2") (pintype "passive"))
    )
    (net (code "36") (name "Net-(U2A-IN+)") (class "Default")
      (node (ref "R2") (pin "2") (pinfunction "2_2") (pintype "passive"))
      (node (ref "R3") (pin "2") (pinfunction "2_2") (pintype "passive"))
      (node (ref "U2") (pin "3") (pinfunction "IN+_3") (pintype "input"))
    )
    (net (code "37") (name "Net-(U2A-IN-)") (class "Default")
      (node (ref "R6") (pin "1") (pinfunction "1_1") (pintype "passive"))
      (node (ref "U2") (pin "2") (pinfunction "IN-_2") (pintype "input"))
    )
    (net (code "38") (name "Net-(U2B-IN+)") (class "Default")
      (node (ref "R4") (pin "2") (pinfunction "2_2") (pintype "passive"))
      (node (ref "R5") (pin "2") (pinfunction "2_2") (pintype "passive"))
      (node (ref "U2") (pin "10") (pinfunction "IN+_10") (pintype "input"))
    )
    (net (code "39") (name "Net-(U2B-IN-)") (class "Default")
      (node (ref "R7") (pin "1") (pinfunction "1_1") (pintype "passive"))
      (node (ref "U2") (pin "9") (pinfunction "IN-_9") (pintype "input"))
    )
    (net (code "40") (name "Net-(U2C-IN+)") (class "Default")
      (node (ref "R8") (pin "2") (pinfunction "2_2") (pintype "passive"))
      (node (ref "R9") (pin "2") (pinfunction "2_2") (pintype "passive"))
      (node (ref "U2") (pin "5") (pinfunction "IN+_5") (pintype "input"))
    )
    (net (code "41") (name "Net-(U2C-IN-)") (class "Default")
      (node (ref "R10") (pin "1") (pinfunction "1_1") (pintype "passive"))
      (node (ref "U2") (pin "6") (pinfunction "IN-_6") (pintype "input"))
    )
    (net (code "42") (name "Net-(U2D-IN+)") (class "Default")
      (node (ref "R11") (pin "2") (pinfunction "2_2") (pintype "passive"))
      (node (ref "R12") (pin "2") (pinfunction "2_2") (pintype "passive"))
      (node (ref "U2") (pin "12") (pinfunction "IN+_12") (pintype "input"))
    )
    (net (code "43") (name "Net-(U2D-IN-)") (class "Default")
      (node (ref "R13") (pin "1") (pinfunction "1_1") (pintype "passive"))
      (node (ref "U2") (pin "13") (pinfunction "IN-_13") (pintype "input"))
    )
    (net (code "44") (name "Net-(U4-A0)") (class "Default")
      (node (ref "R31") (pin "1") (pinfunction "1_1") (pintype "passive"))
      (node (ref "SW2") (pin "2") (pinfunction "2_2") (pintype "bidirectional"))
      (node (ref "U4") (pin "1") (pinfunction "A0_1") (pintype "bidirectional"))
    )
    (net (code "45") (name "Net-(U4-A1)") (class "Default")
      (node (ref "R32") (pin "1") (pinfunction "1_1") (pintype "passive"))
      (node (ref "SW2") (pin "1") (pinfunction "1_1") (pintype "bidirectional"))
      (node (ref "U4") (pin "2") (pinfunction "A1_2") (pintype "bidirectional"))
    )
    (net (code "46") (name "Net-(U4-A2)") (class "Default")
      (node (ref "R33") (pin "1") (pinfunction "1_1") (pintype "passive"))
      (node (ref "U4") (pin "3") (pinfunction "A2_3") (pintype "bidirectional"))
    )
    (net (code "47") (name "Net-(U4-WP)") (class "Default")
      (node (ref "J13") (pin "1") (pinfunction "1_1") (pintype "bidirectional"))
      (node (ref "R30") (pin "2") (pinfunction "2_2") (pintype "passive"))
      (node (ref "U4") (pin "7") (pinfunction "WP_7") (pintype "bidirectional"))
    )
    (net (code "48") (name "SYS_5V") (class "Default")
      (node (ref "C6") (pin "1") (pinfunction "1_1") (pintype "passive"))
      (node (ref "FB2") (pin "1") (pinfunction "1_1") (pintype "passive"))
      (node (ref "P9") (pin "7") (pinfunction "7_7") (pintype "bidirectional"))
      (node (ref "P9") (pin "8") (pinfunction "8_8") (pintype "bidirectional"))
    )
    (net (code "49") (name "VDD_3V3B") (class "Default")
      (node (ref "C3") (pin "1") (pinfunction "1_1") (pintype "passive"))
      (node (ref "FB1") (pin "1") (pinfunction "1_1") (pintype "passive"))
      (node (ref "P9") (pin "3") (pinfunction "3_3") (pintype "bidirectional"))
      (node (ref "P9") (pin "4") (pinfunction "4_4") (pintype "bidirectional"))
    )
    (net (code "50") (name "VDD_ADC") (class "Default")
      (node (ref "C48") (pin "1") (pinfunction "1_1") (pintype "passive"))
      (node (ref "D1") (pin "2") (pinfunction "2_2") (pintype "bidirectional"))
      (node (ref "D2") (pin "2") (pinfunction "2_2") (pintype "bidirectional"))
      (node (ref "D3") (pin "2") (pinfunction "2_2") (pintype "bidirectional"))
      (node (ref "D4") (pin "2") (pinfunction "2_2") (pintype "bidirectional"))
      (node (ref "P9") (pin "32") (pinfunction "32_32") (pintype "bidirectional"))
    )
    (net (code "51") (name "VDD_G") (class "Default")
      (node (ref "C12") (pin "1") (pinfunction "1_1") (pintype "passive"))
      (node (ref "C13") (pin "1") (pinfunction "1_1") (pintype "passive"))
      (node (ref "C16") (pin "1") (pinfunction "1_1") (pintype "passive"))
      (node (ref "C19") (pin "1") (pinfunction "1_1") (pintype "passive"))
      (node (ref "C2") (pin "1") (pinfunction "1_1") (pintype "passive"))
      (node (ref "C22") (pin "1") (pinfunction "1_1") (pintype "passive"))
      (node (ref "C25") (pin "1") (pinfunction "1_1") (pintype "passive"))
      (node (ref "C28") (pin "1") (pinfunction "1_1") (pintype "passive"))
      (node (ref "C31") (pin "1") (pinfunction "1_1") (pintype "passive"))
      (node (ref "C34") (pin "1") (pinfunction "1_1") (pintype "passive"))
      (node (ref "C37") (pin "1") (pinfunction "1_1") (pintype "passive"))
      (node (ref "C42") (pin "1") (pinfunction "1_1") (pintype "passive"))
      (node (ref "C45") (pin "1") (pinfunction "1_1") (pintype "passive"))
      (node (ref "J1") (pin "3") (pinfunction "3_3") (pintype "bidirectional"))
      (node (ref "J10") (pin "3") (pinfunction "3_3") (pintype "bidirectional"))
      (node (ref "J11") (pin "3") (pinfunction "3_3") (pintype "bidirectional"))
      (node (ref "J12") (pin "3") (pinfunction "3_3") (pintype "bidirectional"))
      (node (ref "J2") (pin "3") (pinfunction "3_3") (pintype "bidirectional"))
      (node (ref "J3") (pin "3") (pinfunction "3_3") (pintype "bidirectional"))
      (node (ref "J4") (pin "3") (pinfunction "3_3") (pintype "bidirectional"))
      (node (ref "J5") (pin "3") (pinfunction "3_3") (pintype "bidirectional"))
      (node (ref "J6") (pin "3") (pinfunction "3_3") (pintype "bidirectional"))
      (node (ref "J7") (pin "3") (pinfunction "3_3") (pintype "bidirectional"))
      (node (ref "J8") (pin "3") (pinfunction "3_3") (pintype "bidirectional"))
      (node (ref "J9") (pin "3") (pinfunction "3_3") (pintype "bidirectional"))
      (node (ref "R1") (pin "1") (pinfunction "1_1") (pintype "passive"))
      (node (ref "R15") (pin "2") (pinfunction "2_2") (pintype "passive"))
      (node (ref "R17") (pin "2") (pinfunction "2_2") (pintype "passive"))
      (node (ref "SW1") (pin "COM") (pinfunction "COM_COM") (pintype "bidirectional"))
      (node (ref "U1") (pin "19") (pinfunction "VCCB_19") (pintype "bidirectional"))
    )
    (net (code "52") (name "unconnected-(P8-Pad3)") (class "Default")
      (node (ref "P8") (pin "3") (pinfunction "3_3") (pintype "bidirectional"))
    )
    (net (code "53") (name "unconnected-(P8-Pad4)") (class "Default")
      (node (ref "P8") (pin "4") (pinfunction "4_4") (pintype "bidirectional"))
    )
    (net (code "54") (name "unconnected-(P8-Pad5)") (class "Default")
      (node (ref "P8") (pin "5") (pinfunction "5_5") (pintype "bidirectional"))
    )
    (net (code "55") (name "unconnected-(P8-Pad6)") (class "Default")
      (node (ref "P8") (pin "6") (pinfunction "6_6") (pintype "bidirectional"))
    )
    (net (code "56") (name "unconnected-(P8-Pad7)") (class "Default")
      (node (ref "P8") (pin "7") (pinfunction "7_7") (pintype "bidirectional"))
    )
    (net (code "57") (name "unconnected-(P8-Pad8)") (class "Default")
      (node (ref "P8") (pin "8") (pinfunction "8_8") (pintype "bidirectional"))
    )
    (net (code "58") (name "unconnected-(P8-Pad9)") (class "Default")
      (node (ref "P8") (pin "9") (pinfunction "9_9") (pintype "bidirectional"))
    )
    (net (code "59") (name "unconnected-(P8-Pad10)") (class "Default")
      (node (ref "P8") (pin "10") (pinfunction "10_10") (pintype "bidirectional"))
    )
    (net (code "60") (name "unconnected-(P8-Pad11)") (class "Default")
      (node (ref "P8") (pin "11") (pinfunction "11_11") (pintype "bidirectional"))
    )
    (net (code "61") (name "unconnected-(P8-Pad12)") (class "Default")
      (node (ref "P8") (pin "12") (pinfunction "12_12") (pintype "bidirectional"))
    )
    (net (code "62") (name "unconnected-(P8-Pad13)") (class "Default")
      (node (ref "P8") (pin "13") (pinfunction "13_13") (pintype "bidirectional"))
    )
    (net (code "63") (name "unconnected-(P8-Pad14)") (class "Default")
      (node (ref "P8") (pin "14") (pinfunction "14_14") (pintype "bidirectional"))
    )
    (net (code "64") (name "unconnected-(P8-Pad15)") (class "Default")
      (node (ref "P8") (pin "15") (pinfunction "15_15") (pintype "bidirectional"))
    )
    (net (code "65") (name "unconnected-(P8-Pad16)") (class "Default")
      (node (ref "P8") (pin "16") (pinfunction "16_16") (pintype "bidirectional"))
    )
    (net (code "66") (name "unconnected-(P8-Pad17)") (class "Default")
      (node (ref "P8") (pin "17") (pinfunction "17_17") (pintype "bidirectional"))
    )
    (net (code "67") (name "unconnected-(P8-Pad18)") (class "Default")
      (node (ref "P8") (pin "18") (pinfunction "18_18") (pintype "bidirectional"))
    )
    (net (code "68") (name "unconnected-(P8-Pad19)") (class "Default")
      (node (ref "P8") (pin "19") (pinfunction "19_19") (pintype "bidirectional"))
    )
    (net (code "69") (name "unconnected-(P8-Pad20)") (class "Default")
      (node (ref "P8") (pin "20") (pinfunction "20_20") (pintype "bidirectional"))
    )
    (net (code "70") (name "unconnected-(P8-Pad21)") (class "Default")
      (node (ref "P8") (pin "21") (pinfunction "21_21") (pintype "bidirectional"))
    )
    (net (code "71") (name "unconnected-(P8-Pad22)") (class "Default")
      (node (ref "P8") (pin "22") (pinfunction "22_22") (pintype "bidirectional"))
    )
    (net (code "72") (name "unconnected-(P8-Pad23)") (class "Default")
      (node (ref "P8") (pin "23") (pinfunction "23_23") (pintype "bidirectional"))
    )
    (net (code "73") (name "unconnected-(P8-Pad24)") (class "Default")
      (node (ref "P8") (pin "24") (pinfunction "24_24") (pintype "bidirectional"))
    )
    (net (code "74") (name "unconnected-(P8-Pad25)") (class "Default")
      (node (ref "P8") (pin "25") (pinfunction "25_25") (pintype "bidirectional"))
    )
    (net (code "75") (name "unconnected-(P8-Pad26)") (class "Default")
      (node (ref "P8") (pin "26") (pinfunction "26_26") (pintype "bidirectional"))
    )
    (net (code "76") (name "unconnected-(P8-Pad27)") (class "Default")
      (node (ref "P8") (pin "27") (pinfunction "27_27") (pintype "bidirectional"))
    )
    (net (code "77") (name "unconnected-(P8-Pad28)") (class "Default")
      (node (ref "P8") (pin "28") (pinfunction "28_28") (pintype "bidirectional"))
    )
    (net (code "78") (name "unconnected-(P8-Pad29)") (class "Default")
      (node (ref "P8") (pin "29") (pinfunction "29_29") (pintype "bidirectional"))
    )
    (net (code "79") (name "unconnected-(P8-Pad30)") (class "Default")
      (node (ref "P8") (pin "30") (pinfunction "30_30") (pintype "bidirectional"))
    )
    (net (code "80") (name "unconnected-(P8-Pad31)") (class "Default")
      (node (ref "P8") (pin "31") (pinfunction "31_31") (pintype "bidirectional"))
    )
    (net (code "81") (name "unconnected-(P8-Pad32)") (class "Default")
      (node (ref "P8") (pin "32") (pinfunction "32_32") (pintype "bidirectional"))
    )
    (net (code "82") (name "unconnected-(P8-Pad33)") (class "Default")
      (node (ref "P8") (pin "33") (pinfunction "33_33") (pintype "bidirectional"))
    )
    (net (code "83") (name "unconnected-(P8-Pad34)") (class "Default")
      (node (ref "P8") (pin "34") (pinfunction "34_34") (pintype "bidirectional"))
    )
    (net (code "84") (name "unconnected-(P8-Pad35)") (class "Default")
      (node (ref "P8") (pin "35") (pinfunction "35_35") (pintype "bidirectional"))
    )
    (net (code "85") (name "unconnected-(P8-Pad36)") (class "Default")
      (node (ref "P8") (pin "36") (pinfunction "36_36") (pintype "bidirectional"))
    )
    (net (code "86") (name "unconnected-(P8-Pad37)") (class "Default")
      (node (ref "P8") (pin "37") (pinfunction "37_37") (pintype "bidirectional"))
    )
    (net (code "87") (name "unconnected-(P8-Pad38)") (class "Default")
      (node (ref "P8") (pin "38") (pinfunction "38_38") (pintype "bidirectional"))
    )
    (net (code "88") (name "unconnected-(P8-Pad39)") (class "Default")
      (node (ref "P8") (pin "39") (pinfunction "39_39") (pintype "bidirectional"))
    )
    (net (code "89") (name "unconnected-(P8-Pad40)") (class "Default")
      (node (ref "P8") (pin "40") (pinfunction "40_40") (pintype "bidirectional"))
    )
    (net (code "90") (name "unconnected-(P8-Pad41)") (class "Default")
      (node (ref "P8") (pin "41") (pinfunction "41_41") (pintype "bidirectional"))
    )
    (net (code "91") (name "unconnected-(P8-Pad42)") (class "Default")
      (node (ref "P8") (pin "42") (pinfunction "42_42") (pintype "bidirectional"))
    )
    (net (code "92") (name "unconnected-(P8-Pad44)") (class "Default")
      (node (ref "P8") (pin "44") (pinfunction "44_44") (pintype "bidirectional"))
    )
    (net (code "93") (name "unconnected-(P8-Pad45)") (class "Default")
      (node (ref "P8") (pin "45") (pinfunction "45_45") (pintype "bidirectional"))
    )
    (net (code "94") (name "unconnected-(P8-Pad46)") (class "Default")
      (node (ref "P8") (pin "46") (pinfunction "46_46") (pintype "bidirectional"))
    )
    (net (code "95") (name "unconnected-(P9-Pad5)") (class "Default")
      (node (ref "P9") (pin "5") (pinfunction "5_5") (pintype "bidirectional"))
    )
    (net (code "96") (name "unconnected-(P9-Pad6)") (class "Default")
      (node (ref "P9") (pin "6") (pinfunction "6_6") (pintype "bidirectional"))
    )
    (net (code "97") (name "unconnected-(P9-Pad9)") (class "Default")
      (node (ref "P9") (pin "9") (pinfunction "9_9") (pintype "bidirectional"))
    )
    (net (code "98") (name "unconnected-(P9-Pad10)") (class "Default")
      (node (ref "P9") (pin "10") (pinfunction "10_10") (pintype "bidirectional"))
    )
    (net (code "99") (name "unconnected-(P9-Pad12)") (class "Default")
      (node (ref "P9") (pin "12") (pinfunction "12_12") (pintype "bidirectional"))
    )
    (net (code "100") (name "unconnected-(P9-Pad15)") (class "Default")
      (node (ref "P9") (pin "15") (pinfunction "15_15") (pintype "bidirectional"))
    )
    (net (code "101") (name "unconnected-(P9-Pad17)") (class "Default")
      (node (ref "P9") (pin "17") (pinfunction "17_17") (pintype "bidirectional"))
    )
    (net (code "102") (name "unconnected-(P9-Pad18)") (class "Default")
      (node (ref "P9") (pin "18") (pinfunction "18_18") (pintype "bidirectional"))
    )
    (net (code "103") (name "unconnected-(P9-Pad21)") (class "Default")
      (node (ref "P9") (pin "21") (pinfunction "21_21") (pintype "bidirectional"))
    )
    (net (code "104") (name "unconnected-(P9-Pad22)") (class "Default")
      (node (ref "P9") (pin "22") (pinfunction "22_22") (pintype "bidirectional"))
    )
    (net (code "105") (name "unconnected-(P9-Pad23)") (class "Default")
      (node (ref "P9") (pin "23") (pinfunction "23_23") (pintype "bidirectional"))
    )
    (net (code "106") (name "unconnected-(P9-Pad28)") (class "Default")
      (node (ref "P9") (pin "28") (pinfunction "28_28") (pintype "bidirectional"))
    )
    (net (code "107") (name "unconnected-(P9-Pad29)") (class "Default")
      (node (ref "P9") (pin "29") (pinfunction "29_29") (pintype "bidirectional"))
    )
    (net (code "108") (name "unconnected-(P9-Pad30)") (class "Default")
      (node (ref "P9") (pin "30") (pinfunction "30_30") (pintype "bidirectional"))
    )
    (net (code "109") (name "unconnected-(P9-Pad31)") (class "Default")
      (node (ref "P9") (pin "31") (pinfunction "31_31") (pintype "bidirectional"))
    )
    (net (code "110") (name "unconnected-(P9-Pad33)") (class "Default")
      (node (ref "P9") (pin "33") (pinfunction "33_33") (pintype "bidirectional"))
    )
    (net (code "111") (name "unconnected-(P9-Pad34)") (class "Default")
      (node (ref "P9") (pin "34") (pinfunction "34_34") (pintype "bidirectional"))
    )
    (net (code "112") (name "unconnected-(P9-Pad35)") (class "Default")
      (node (ref "P9") (pin "35") (pinfunction "35_35") (pintype "bidirectional"))
    )
    (net (code "113") (name "unconnected-(P9-Pad36)") (class "Default")
      (node (ref "P9") (pin "36") (pinfunction "36_36") (pintype "bidirectional"))
    )
    (net (code "114") (name "unconnected-(P9-Pad41)") (class "Default")
      (node (ref "P9") (pin "41") (pinfunction "41_41") (pintype "bidirectional"))
    )
    (net (code "115") (name "unconnected-(P9-Pad42)") (class "Default")
      (node (ref "P9") (pin "42") (pinfunction "42_42") (pintype "bidirectional"))
    )
    (net (code "116") (name "unconnected-(SW1-PadSS1)") (class "Default")
      (node (ref "SW1") (pin "SS1") (pinfunction "SS1_SS1") (pintype "bidirectional"))
    )
    (net (code "117") (name "unconnected-(SW1-PadSS2)") (class "Default")
      (node (ref "SW1") (pin "SS2") (pinfunction "SS2_SS2") (pintype "bidirectional"))
    )
    (net (code "118") (name "unconnected-(SW1-PadSS3)") (class "Default")
      (node (ref "SW1") (pin "SS3") (pinfunction "SS3_SS3") (pintype "bidirectional"))
    )
    (net (code "119") (name "unconnected-(SW1-PadSS4)") (class "Default")
      (node (ref "SW1") (pin "SS4") (pinfunction "SS4_SS4") (pintype "bidirectional"))
    )
  )
)
